# LEDjets.net
KiCad netlist of a schematic drawn in EAGLE
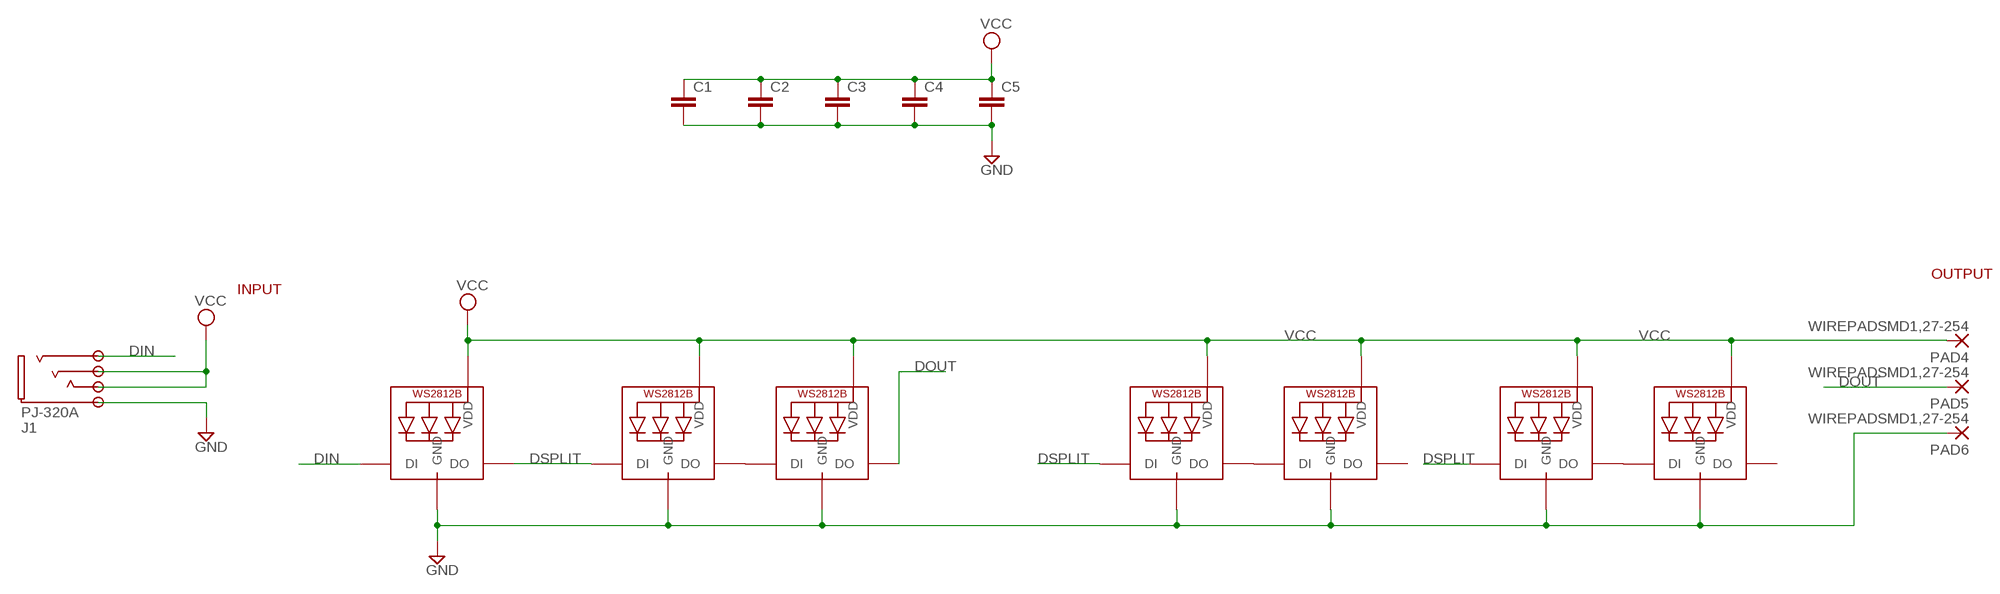
[diagram p0: schematic, sheet 1]

(export (version "E")
  (design (tool "Eeschema 10.0.6"))
  (components
    (comp (ref "C1")
      (value "C-EUC0805K")
      (footprint "eagle-import:C0805K")
      (libsource (lib "eagle-import") (part "C-EUC0805K"))
    )
    (comp (ref "C2")
      (value "C-EUC0805K")
      (footprint "eagle-import:C0805K")
      (libsource (lib "eagle-import") (part "C-EUC0805K"))
    )
    (comp (ref "C3")
      (value "C-EUC0805K")
      (footprint "eagle-import:C0805K")
      (libsource (lib "eagle-import") (part "C-EUC0805K"))
    )
    (comp (ref "C4")
      (value "C-EUC0805K")
      (footprint "eagle-import:C0805K")
      (libsource (lib "eagle-import") (part "C-EUC0805K"))
    )
    (comp (ref "C5")
      (value "C-EUC0805K")
      (footprint "eagle-import:C0805K")
      (libsource (lib "eagle-import") (part "C-EUC0805K"))
    )
    (comp (ref "J1")
      (value "PJ-320A")
      (footprint "eagle-import:PJ-320A")
      (libsource (lib "eagle-import") (part "PJ-320A"))
    )
    (comp (ref "LED1")
      (value "WS2812B5050")
      (footprint "eagle-import:WS2812B")
      (libsource (lib "eagle-import") (part "WS2812B5050"))
    )
    (comp (ref "LED2")
      (value "WS2812B5050")
      (footprint "eagle-import:WS2812B")
      (libsource (lib "eagle-import") (part "WS2812B5050"))
    )
    (comp (ref "LED3")
      (value "WS2812B5050")
      (footprint "eagle-import:WS2812B")
      (libsource (lib "eagle-import") (part "WS2812B5050"))
    )
    (comp (ref "LED4")
      (value "WS2812B5050")
      (footprint "eagle-import:WS2812B")
      (libsource (lib "eagle-import") (part "WS2812B5050"))
    )
    (comp (ref "LED5")
      (value "WS2812B5050")
      (footprint "eagle-import:WS2812B")
      (libsource (lib "eagle-import") (part "WS2812B5050"))
    )
    (comp (ref "LED6")
      (value "WS2812B5050")
      (footprint "eagle-import:WS2812B")
      (libsource (lib "eagle-import") (part "WS2812B5050"))
    )
    (comp (ref "LED7")
      (value "WS2812B5050")
      (footprint "eagle-import:WS2812B")
      (libsource (lib "eagle-import") (part "WS2812B5050"))
    )
    (comp (ref "PAD4")
      (value "WIREPADSMD1,27-254")
      (footprint "eagle-import:SMD1,27-2,54")
      (libsource (lib "eagle-import") (part "WIREPADSMD1,27-254"))
    )
    (comp (ref "PAD5")
      (value "WIREPADSMD1,27-254")
      (footprint "eagle-import:SMD1,27-2,54")
      (libsource (lib "eagle-import") (part "WIREPADSMD1,27-254"))
    )
    (comp (ref "PAD6")
      (value "WIREPADSMD1,27-254")
      (footprint "eagle-import:SMD1,27-2,54")
      (libsource (lib "eagle-import") (part "WIREPADSMD1,27-254"))
    )
  )
  (nets
    (net (code "1") (name "/DIN") (class "Default")
      (node (ref "J1") (pin "2") (pinfunction "2_2") (pintype "bidirectional"))
      (node (ref "LED1") (pin "4-DIN") (pinfunction "DI_4-DIN") (pintype "input"))
    )
    (net (code "2") (name "/DOUT") (class "Default")
      (node (ref "LED3") (pin "2-DOUT") (pinfunction "DO_2-DOUT") (pintype "output"))
      (node (ref "PAD5") (pin "1") (pinfunction "P_1") (pintype "passive"))
    )
    (net (code "3") (name "/DSPLIT") (class "Default")
      (node (ref "LED1") (pin "2-DOUT") (pinfunction "DO_2-DOUT") (pintype "output"))
      (node (ref "LED2") (pin "4-DIN") (pinfunction "DI_4-DIN") (pintype "input"))
      (node (ref "LED4") (pin "4-DIN") (pinfunction "DI_4-DIN") (pintype "input"))
      (node (ref "LED6") (pin "4-DIN") (pinfunction "DI_4-DIN") (pintype "input"))
    )
    (net (code "4") (name "GND") (class "Default")
      (node (ref "C1") (pin "2") (pinfunction "2_2") (pintype "passive"))
      (node (ref "C2") (pin "2") (pinfunction "2_2") (pintype "passive"))
      (node (ref "C3") (pin "2") (pinfunction "2_2") (pintype "passive"))
      (node (ref "C4") (pin "2") (pinfunction "2_2") (pintype "passive"))
      (node (ref "C5") (pin "2") (pinfunction "2_2") (pintype "passive"))
      (node (ref "J1") (pin "5") (pinfunction "5_5") (pintype "power_in"))
      (node (ref "LED1") (pin "3-GND") (pinfunction "GND_3-GND") (pintype "power_in"))
      (node (ref "LED2") (pin "3-GND") (pinfunction "GND_3-GND") (pintype "power_in"))
      (node (ref "LED3") (pin "3-GND") (pinfunction "GND_3-GND") (pintype "power_in"))
      (node (ref "LED4") (pin "3-GND") (pinfunction "GND_3-GND") (pintype "power_in"))
      (node (ref "LED5") (pin "3-GND") (pinfunction "GND_3-GND") (pintype "power_in"))
      (node (ref "LED6") (pin "3-GND") (pinfunction "GND_3-GND") (pintype "power_in"))
      (node (ref "LED7") (pin "3-GND") (pinfunction "GND_3-GND") (pintype "power_in"))
      (node (ref "PAD6") (pin "1") (pinfunction "P_1") (pintype "passive"))
    )
    (net (code "5") (name "Net-(LED2-DO)") (class "Default")
      (node (ref "LED2") (pin "2-DOUT") (pinfunction "DO_2-DOUT") (pintype "output"))
      (node (ref "LED3") (pin "4-DIN") (pinfunction "DI_4-DIN") (pintype "input"))
    )
    (net (code "6") (name "Net-(LED4-DO)") (class "Default")
      (node (ref "LED4") (pin "2-DOUT") (pinfunction "DO_2-DOUT") (pintype "output"))
      (node (ref "LED5") (pin "4-DIN") (pinfunction "DI_4-DIN") (pintype "input"))
    )
    (net (code "7") (name "Net-(LED6-DO)") (class "Default")
      (node (ref "LED6") (pin "2-DOUT") (pinfunction "DO_2-DOUT") (pintype "output"))
      (node (ref "LED7") (pin "4-DIN") (pinfunction "DI_4-DIN") (pintype "input"))
    )
    (net (code "8") (name "VCC") (class "Default")
      (node (ref "C1") (pin "1") (pinfunction "1_1") (pintype "passive"))
      (node (ref "C2") (pin "1") (pinfunction "1_1") (pintype "passive"))
      (node (ref "C3") (pin "1") (pinfunction "1_1") (pintype "passive"))
      (node (ref "C4") (pin "1") (pinfunction "1_1") (pintype "passive"))
      (node (ref "C5") (pin "1") (pinfunction "1_1") (pintype "passive"))
      (node (ref "J1") (pin "3") (pinfunction "3_3") (pintype "bidirectional"))
      (node (ref "J1") (pin "4") (pinfunction "4_4") (pintype "bidirectional"))
      (node (ref "LED1") (pin "1-VDD") (pinfunction "VDD_1-VDD") (pintype "power_in"))
      (node (ref "LED2") (pin "1-VDD") (pinfunction "VDD_1-VDD") (pintype "power_in"))
      (node (ref "LED3") (pin "1-VDD") (pinfunction "VDD_1-VDD") (pintype "power_in"))
      (node (ref "LED4") (pin "1-VDD") (pinfunction "VDD_1-VDD") (pintype "power_in"))
      (node (ref "LED5") (pin "1-VDD") (pinfunction "VDD_1-VDD") (pintype "power_in"))
      (node (ref "LED6") (pin "1-VDD") (pinfunction "VDD_1-VDD") (pintype "power_in"))
      (node (ref "LED7") (pin "1-VDD") (pinfunction "VDD_1-VDD") (pintype "power_in"))
      (node (ref "PAD4") (pin "1") (pinfunction "P_1") (pintype "passive"))
    )
    (net (code "9") (name "unconnected-(LED5-DO-Pad2-DOUT)") (class "Default")
      (node (ref "LED5") (pin "2-DOUT") (pinfunction "DO_2-DOUT") (pintype "output"))
    )
    (net (code "10") (name "unconnected-(LED7-DO-Pad2-DOUT)") (class "Default")
      (node (ref "LED7") (pin "2-DOUT") (pinfunction "DO_2-DOUT") (pintype "output"))
    )
  )
)
